# Display_Alt.net
KiCad netlist of a schematic drawn in Altium Designer
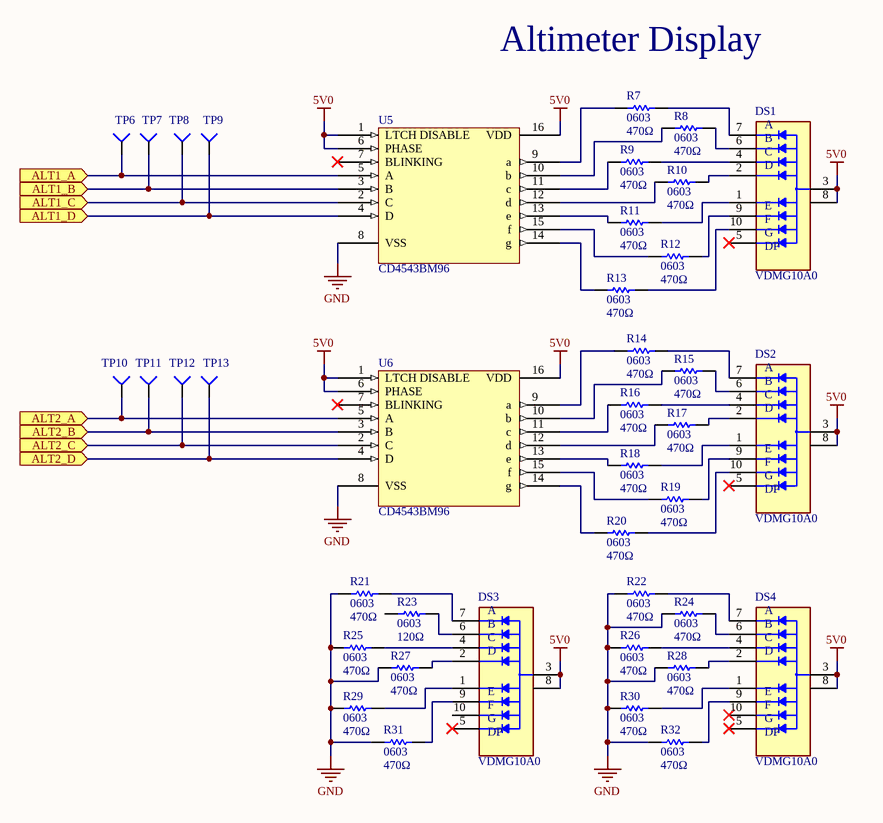
[diagram p0: Display Alt.SchDoc]

(export (version "E")
  (design (tool "Eeschema 10.0.6"))
  (components
    (comp (ref "DS1")
      (value "VDMG10A0")
      (footprint "DISPLAY_VDMG10A0")
      (description "Smart/Normal 7 Seg Numeric LED Display")
      (fields (field (name "MANUFACTURER") "Vishay Semiconductors"))
      (libsource (lib "SKALE_LIB") (part "7 SEG DISPLAY - VDMG10A0"))
    )
    (comp (ref "DS2")
      (value "VDMG10A0")
      (footprint "DISPLAY_VDMG10A0")
      (description "Smart/Normal 7 Seg Numeric LED Display")
      (fields (field (name "MANUFACTURER") "Vishay Semiconductors"))
      (libsource (lib "SKALE_LIB") (part "7 SEG DISPLAY - VDMG10A0"))
    )
    (comp (ref "DS3")
      (value "VDMG10A0")
      (footprint "DISPLAY_VDMG10A0")
      (description "Smart/Normal 7 Seg Numeric LED Display")
      (fields (field (name "MANUFACTURER") "Vishay Semiconductors"))
      (libsource (lib "SKALE_LIB") (part "7 SEG DISPLAY - VDMG10A0"))
    )
    (comp (ref "DS4")
      (value "VDMG10A0")
      (footprint "DISPLAY_VDMG10A0")
      (description "Smart/Normal 7 Seg Numeric LED Display")
      (fields (field (name "MANUFACTURER") "Vishay Semiconductors"))
      (libsource (lib "SKALE_LIB") (part "7 SEG DISPLAY - VDMG10A0"))
    )
    (comp (ref "R7")
      (value "470Ω")
      (footprint "RES0603")
      (description "RES 470 OHM 1% 1/10W 0603")
      (fields (field (name "FOOTPRINT SIZE") "0603") (field (name "Comment") "470R 1%"))
      (libsource (lib "SKALE_LIB") (part "RES_470Ω_0603_1%"))
    )
    (comp (ref "R8")
      (value "470Ω")
      (footprint "RES0603")
      (description "RES 470 OHM 1% 1/10W 0603")
      (fields (field (name "FOOTPRINT SIZE") "0603") (field (name "Comment") "470R 1%"))
      (libsource (lib "SKALE_LIB") (part "RES_470Ω_0603_1%"))
    )
    (comp (ref "R9")
      (value "470Ω")
      (footprint "RES0603")
      (description "RES 470 OHM 1% 1/10W 0603")
      (fields (field (name "FOOTPRINT SIZE") "0603") (field (name "Comment") "470R 1%"))
      (libsource (lib "SKALE_LIB") (part "RES_470Ω_0603_1%"))
    )
    (comp (ref "R10")
      (value "470Ω")
      (footprint "RES0603")
      (description "RES 470 OHM 1% 1/10W 0603")
      (fields (field (name "FOOTPRINT SIZE") "0603") (field (name "Comment") "470R 1%"))
      (libsource (lib "SKALE_LIB") (part "RES_470Ω_0603_1%"))
    )
    (comp (ref "R11")
      (value "470Ω")
      (footprint "RES0603")
      (description "RES 470 OHM 1% 1/10W 0603")
      (fields (field (name "FOOTPRINT SIZE") "0603") (field (name "Comment") "470R 1%"))
      (libsource (lib "SKALE_LIB") (part "RES_470Ω_0603_1%"))
    )
    (comp (ref "R12")
      (value "470Ω")
      (footprint "RES0603")
      (description "RES 470 OHM 1% 1/10W 0603")
      (fields (field (name "FOOTPRINT SIZE") "0603") (field (name "Comment") "470R 1%"))
      (libsource (lib "SKALE_LIB") (part "RES_470Ω_0603_1%"))
    )
    (comp (ref "R13")
      (value "470Ω")
      (footprint "RES0603")
      (description "RES 470 OHM 1% 1/10W 0603")
      (fields (field (name "FOOTPRINT SIZE") "0603") (field (name "Comment") "470R 1%"))
      (libsource (lib "SKALE_LIB") (part "RES_470Ω_0603_1%"))
    )
    (comp (ref "R14")
      (value "470Ω")
      (footprint "RES0603")
      (description "RES 470 OHM 1% 1/10W 0603")
      (fields (field (name "FOOTPRINT SIZE") "0603") (field (name "Comment") "470R 1%"))
      (libsource (lib "SKALE_LIB") (part "RES_470Ω_0603_1%"))
    )
    (comp (ref "R15")
      (value "470Ω")
      (footprint "RES0603")
      (description "RES 470 OHM 1% 1/10W 0603")
      (fields (field (name "FOOTPRINT SIZE") "0603") (field (name "Comment") "470R 1%"))
      (libsource (lib "SKALE_LIB") (part "RES_470Ω_0603_1%"))
    )
    (comp (ref "R16")
      (value "470Ω")
      (footprint "RES0603")
      (description "RES 470 OHM 1% 1/10W 0603")
      (fields (field (name "FOOTPRINT SIZE") "0603") (field (name "Comment") "470R 1%"))
      (libsource (lib "SKALE_LIB") (part "RES_470Ω_0603_1%"))
    )
    (comp (ref "R17")
      (value "470Ω")
      (footprint "RES0603")
      (description "RES 470 OHM 1% 1/10W 0603")
      (fields (field (name "FOOTPRINT SIZE") "0603") (field (name "Comment") "470R 1%"))
      (libsource (lib "SKALE_LIB") (part "RES_470Ω_0603_1%"))
    )
    (comp (ref "R18")
      (value "470Ω")
      (footprint "RES0603")
      (description "RES 470 OHM 1% 1/10W 0603")
      (fields (field (name "FOOTPRINT SIZE") "0603") (field (name "Comment") "470R 1%"))
      (libsource (lib "SKALE_LIB") (part "RES_470Ω_0603_1%"))
    )
    (comp (ref "R19")
      (value "470Ω")
      (footprint "RES0603")
      (description "RES 470 OHM 1% 1/10W 0603")
      (fields (field (name "FOOTPRINT SIZE") "0603") (field (name "Comment") "470R 1%"))
      (libsource (lib "SKALE_LIB") (part "RES_470Ω_0603_1%"))
    )
    (comp (ref "R20")
      (value "470Ω")
      (footprint "RES0603")
      (description "RES 470 OHM 1% 1/10W 0603")
      (fields (field (name "FOOTPRINT SIZE") "0603") (field (name "Comment") "470R 1%"))
      (libsource (lib "SKALE_LIB") (part "RES_470Ω_0603_1%"))
    )
    (comp (ref "R21")
      (value "470Ω")
      (footprint "RES0603")
      (description "RES 470 OHM 1% 1/10W 0603")
      (fields (field (name "FOOTPRINT SIZE") "0603") (field (name "Comment") "470R 1%"))
      (libsource (lib "SKALE_LIB") (part "RES_470Ω_0603_1%"))
    )
    (comp (ref "R22")
      (value "470Ω")
      (footprint "RES0603")
      (description "RES 470 OHM 1% 1/10W 0603")
      (fields (field (name "FOOTPRINT SIZE") "0603") (field (name "Comment") "470R 1%"))
      (libsource (lib "SKALE_LIB") (part "RES_470Ω_0603_1%"))
    )
    (comp (ref "R23")
      (value "120Ω")
      (footprint "RES0603")
      (description "RES 120 OHM 5% 1/10W 0603")
      (fields (field (name "PACKAGE/FOOTPRINT") "0603") (field (name "Comment") "RES_120Ω_0603"))
      (libsource (lib "SKALE_LIB") (part "RES_120Ω_0603_5%"))
    )
    (comp (ref "R24")
      (value "470Ω")
      (footprint "RES0603")
      (description "RES 470 OHM 1% 1/10W 0603")
      (fields (field (name "FOOTPRINT SIZE") "0603") (field (name "Comment") "470R 1%"))
      (libsource (lib "SKALE_LIB") (part "RES_470Ω_0603_1%"))
    )
    (comp (ref "R25")
      (value "470Ω")
      (footprint "RES0603")
      (description "RES 470 OHM 1% 1/10W 0603")
      (fields (field (name "FOOTPRINT SIZE") "0603") (field (name "Comment") "470R 1%"))
      (libsource (lib "SKALE_LIB") (part "RES_470Ω_0603_1%"))
    )
    (comp (ref "R26")
      (value "470Ω")
      (footprint "RES0603")
      (description "RES 470 OHM 1% 1/10W 0603")
      (fields (field (name "FOOTPRINT SIZE") "0603") (field (name "Comment") "470R 1%"))
      (libsource (lib "SKALE_LIB") (part "RES_470Ω_0603_1%"))
    )
    (comp (ref "R27")
      (value "470Ω")
      (footprint "RES0603")
      (description "RES 470 OHM 1% 1/10W 0603")
      (fields (field (name "FOOTPRINT SIZE") "0603") (field (name "Comment") "470R 1%"))
      (libsource (lib "SKALE_LIB") (part "RES_470Ω_0603_1%"))
    )
    (comp (ref "R28")
      (value "470Ω")
      (footprint "RES0603")
      (description "RES 470 OHM 1% 1/10W 0603")
      (fields (field (name "FOOTPRINT SIZE") "0603") (field (name "Comment") "470R 1%"))
      (libsource (lib "SKALE_LIB") (part "RES_470Ω_0603_1%"))
    )
    (comp (ref "R29")
      (value "470Ω")
      (footprint "RES0603")
      (description "RES 470 OHM 1% 1/10W 0603")
      (fields (field (name "FOOTPRINT SIZE") "0603") (field (name "Comment") "470R 1%"))
      (libsource (lib "SKALE_LIB") (part "RES_470Ω_0603_1%"))
    )
    (comp (ref "R30")
      (value "470Ω")
      (footprint "RES0603")
      (description "RES 470 OHM 1% 1/10W 0603")
      (fields (field (name "FOOTPRINT SIZE") "0603") (field (name "Comment") "470R 1%"))
      (libsource (lib "SKALE_LIB") (part "RES_470Ω_0603_1%"))
    )
    (comp (ref "R31")
      (value "470Ω")
      (footprint "RES0603")
      (description "RES 470 OHM 1% 1/10W 0603")
      (fields (field (name "FOOTPRINT SIZE") "0603") (field (name "Comment") "470R 1%"))
      (libsource (lib "SKALE_LIB") (part "RES_470Ω_0603_1%"))
    )
    (comp (ref "R32")
      (value "470Ω")
      (footprint "RES0603")
      (description "RES 470 OHM 1% 1/10W 0603")
      (fields (field (name "FOOTPRINT SIZE") "0603") (field (name "Comment") "470R 1%"))
      (libsource (lib "SKALE_LIB") (part "RES_470Ω_0603_1%"))
    )
    (comp (ref "TP6")
      (value "TESTPT")
      (footprint "TESTPT SQUARE")
      (libsource (lib "SKALE_LIB") (part "TESTPT SQUARE"))
    )
    (comp (ref "TP7")
      (value "TESTPT")
      (footprint "TESTPT SQUARE")
      (libsource (lib "SKALE_LIB") (part "TESTPT SQUARE"))
    )
    (comp (ref "TP8")
      (value "TESTPT")
      (footprint "TESTPT SQUARE")
      (libsource (lib "SKALE_LIB") (part "TESTPT SQUARE"))
    )
    (comp (ref "TP9")
      (value "TESTPT")
      (footprint "TESTPT SQUARE")
      (libsource (lib "SKALE_LIB") (part "TESTPT SQUARE"))
    )
    (comp (ref "TP10")
      (value "TESTPT")
      (footprint "TESTPT SQUARE")
      (libsource (lib "SKALE_LIB") (part "TESTPT SQUARE"))
    )
    (comp (ref "TP11")
      (value "TESTPT")
      (footprint "TESTPT SQUARE")
      (libsource (lib "SKALE_LIB") (part "TESTPT SQUARE"))
    )
    (comp (ref "TP12")
      (value "TESTPT")
      (footprint "TESTPT SQUARE")
      (libsource (lib "SKALE_LIB") (part "TESTPT SQUARE"))
    )
    (comp (ref "TP13")
      (value "TESTPT")
      (footprint "TESTPT SQUARE")
      (libsource (lib "SKALE_LIB") (part "TESTPT SQUARE"))
    )
    (comp (ref "U5")
      (value "CD4543BM96")
      (footprint "SOIC127P600X175-16N")
      (description "Seven Segment Decoder/Driver, 4000/14000/40000 Series, Configurable Output, CMOS, PDSO16")
      (fields (field (name "MANUFACTURER") "Texas Instruments"))
      (libsource (lib "SKALE_LIB") (part "7 SEG DISPLAY IC"))
    )
    (comp (ref "U6")
      (value "CD4543BM96")
      (footprint "SOIC127P600X175-16N")
      (description "Seven Segment Decoder/Driver, 4000/14000/40000 Series, Configurable Output, CMOS, PDSO16")
      (fields (field (name "MANUFACTURER") "Texas Instruments"))
      (libsource (lib "SKALE_LIB") (part "7 SEG DISPLAY IC"))
    )
  )
  (nets
    (net (code "1") (name "/ALT1_A") (class "Default")
      (node (ref "TP6") (pin "1") (pinfunction "=value_1") (pintype "passive"))
      (node (ref "U5") (pin "5") (pinfunction "A_5") (pintype "input"))
    )
    (net (code "2") (name "/ALT1_B") (class "Default")
      (node (ref "TP7") (pin "1") (pinfunction "=value_1") (pintype "passive"))
      (node (ref "U5") (pin "3") (pinfunction "B_3") (pintype "input"))
    )
    (net (code "3") (name "/ALT1_C") (class "Default")
      (node (ref "TP8") (pin "1") (pinfunction "=value_1") (pintype "passive"))
      (node (ref "U5") (pin "2") (pinfunction "C_2") (pintype "input"))
    )
    (net (code "4") (name "/ALT1_D") (class "Default")
      (node (ref "TP9") (pin "1") (pinfunction "=value_1") (pintype "passive"))
      (node (ref "U5") (pin "4") (pinfunction "D_4") (pintype "input"))
    )
    (net (code "5") (name "/ALT2_A") (class "Default")
      (node (ref "TP10") (pin "1") (pinfunction "=value_1") (pintype "passive"))
      (node (ref "U6") (pin "5") (pinfunction "A_5") (pintype "input"))
    )
    (net (code "6") (name "/ALT2_B") (class "Default")
      (node (ref "TP11") (pin "1") (pinfunction "=value_1") (pintype "passive"))
      (node (ref "U6") (pin "3") (pinfunction "B_3") (pintype "input"))
    )
    (net (code "7") (name "/ALT2_C") (class "Default")
      (node (ref "TP12") (pin "1") (pinfunction "=value_1") (pintype "passive"))
      (node (ref "U6") (pin "2") (pinfunction "C_2") (pintype "input"))
    )
    (net (code "8") (name "/ALT2_D") (class "Default")
      (node (ref "TP13") (pin "1") (pinfunction "=value_1") (pintype "passive"))
      (node (ref "U6") (pin "4") (pinfunction "D_4") (pintype "input"))
    )
    (net (code "9") (name "5V0") (class "Default")
      (node (ref "DS1") (pin "3") (pinfunction "ANODE_3") (pintype "passive"))
      (node (ref "DS1") (pin "8") (pinfunction "ANODE_8") (pintype "passive"))
      (node (ref "DS2") (pin "3") (pinfunction "ANODE_3") (pintype "passive"))
      (node (ref "DS2") (pin "8") (pinfunction "ANODE_8") (pintype "passive"))
      (node (ref "DS3") (pin "3") (pinfunction "ANODE_3") (pintype "passive"))
      (node (ref "DS3") (pin "8") (pinfunction "ANODE_8") (pintype "passive"))
      (node (ref "DS4") (pin "3") (pinfunction "ANODE_3") (pintype "passive"))
      (node (ref "DS4") (pin "8") (pinfunction "ANODE_8") (pintype "passive"))
      (node (ref "U5") (pin "1") (pinfunction "LTCH_DISABLE_1") (pintype "input"))
      (node (ref "U5") (pin "16") (pinfunction "VDD_16") (pintype "power_in"))
      (node (ref "U5") (pin "6") (pinfunction "PHASE_6") (pintype "input"))
      (node (ref "U6") (pin "1") (pinfunction "LTCH_DISABLE_1") (pintype "input"))
      (node (ref "U6") (pin "16") (pinfunction "VDD_16") (pintype "power_in"))
      (node (ref "U6") (pin "6") (pinfunction "PHASE_6") (pintype "input"))
    )
    (net (code "10") (name "GND") (class "Default")
      (node (ref "R21") (pin "1") (pinfunction "1_1") (pintype "passive"))
      (node (ref "R22") (pin "1") (pinfunction "1_1") (pintype "passive"))
      (node (ref "R24") (pin "1") (pinfunction "1_1") (pintype "passive"))
      (node (ref "R25") (pin "1") (pinfunction "1_1") (pintype "passive"))
      (node (ref "R26") (pin "1") (pinfunction "1_1") (pintype "passive"))
      (node (ref "R27") (pin "1") (pinfunction "1_1") (pintype "passive"))
      (node (ref "R28") (pin "1") (pinfunction "1_1") (pintype "passive"))
      (node (ref "R29") (pin "1") (pinfunction "1_1") (pintype "passive"))
      (node (ref "R30") (pin "1") (pinfunction "1_1") (pintype "passive"))
      (node (ref "R31") (pin "1") (pinfunction "1_1") (pintype "passive"))
      (node (ref "R32") (pin "1") (pinfunction "1_1") (pintype "passive"))
      (node (ref "U5") (pin "8") (pinfunction "VSS_8") (pintype "power_in"))
      (node (ref "U6") (pin "8") (pinfunction "VSS_8") (pintype "power_in"))
    )
    (net (code "11") (name "Net-(DS1-A)") (class "Default")
      (node (ref "DS1") (pin "7") (pinfunction "A_7") (pintype "passive"))
      (node (ref "R7") (pin "2") (pinfunction "2_2") (pintype "passive"))
    )
    (net (code "12") (name "Net-(DS1-B)") (class "Default")
      (node (ref "DS1") (pin "6") (pinfunction "B_6") (pintype "passive"))
      (node (ref "R8") (pin "2") (pinfunction "2_2") (pintype "passive"))
    )
    (net (code "13") (name "Net-(DS1-C)") (class "Default")
      (node (ref "DS1") (pin "4") (pinfunction "C_4") (pintype "passive"))
      (node (ref "R9") (pin "2") (pinfunction "2_2") (pintype "passive"))
    )
    (net (code "14") (name "Net-(DS1-D)") (class "Default")
      (node (ref "DS1") (pin "2") (pinfunction "D_2") (pintype "passive"))
      (node (ref "R10") (pin "2") (pinfunction "2_2") (pintype "passive"))
    )
    (net (code "15") (name "Net-(DS1-E)") (class "Default")
      (node (ref "DS1") (pin "1") (pinfunction "E_1") (pintype "passive"))
      (node (ref "R11") (pin "2") (pinfunction "2_2") (pintype "passive"))
    )
    (net (code "16") (name "Net-(DS1-F)") (class "Default")
      (node (ref "DS1") (pin "9") (pinfunction "F_9") (pintype "passive"))
      (node (ref "R12") (pin "2") (pinfunction "2_2") (pintype "passive"))
    )
    (net (code "17") (name "Net-(DS1-G)") (class "Default")
      (node (ref "DS1") (pin "10") (pinfunction "G_10") (pintype "passive"))
      (node (ref "R13") (pin "2") (pinfunction "2_2") (pintype "passive"))
    )
    (net (code "18") (name "Net-(DS2-A)") (class "Default")
      (node (ref "DS2") (pin "7") (pinfunction "A_7") (pintype "passive"))
      (node (ref "R14") (pin "2") (pinfunction "2_2") (pintype "passive"))
    )
    (net (code "19") (name "Net-(DS2-B)") (class "Default")
      (node (ref "DS2") (pin "6") (pinfunction "B_6") (pintype "passive"))
      (node (ref "R15") (pin "2") (pinfunction "2_2") (pintype "passive"))
    )
    (net (code "20") (name "Net-(DS2-C)") (class "Default")
      (node (ref "DS2") (pin "4") (pinfunction "C_4") (pintype "passive"))
      (node (ref "R16") (pin "2") (pinfunction "2_2") (pintype "passive"))
    )
    (net (code "21") (name "Net-(DS2-D)") (class "Default")
      (node (ref "DS2") (pin "2") (pinfunction "D_2") (pintype "passive"))
      (node (ref "R17") (pin "2") (pinfunction "2_2") (pintype "passive"))
    )
    (net (code "22") (name "Net-(DS2-E)") (class "Default")
      (node (ref "DS2") (pin "1") (pinfunction "E_1") (pintype "passive"))
      (node (ref "R18") (pin "2") (pinfunction "2_2") (pintype "passive"))
    )
    (net (code "23") (name "Net-(DS2-F)") (class "Default")
      (node (ref "DS2") (pin "9") (pinfunction "F_9") (pintype "passive"))
      (node (ref "R19") (pin "2") (pinfunction "2_2") (pintype "passive"))
    )
    (net (code "24") (name "Net-(DS2-G)") (class "Default")
      (node (ref "DS2") (pin "10") (pinfunction "G_10") (pintype "passive"))
      (node (ref "R20") (pin "2") (pinfunction "2_2") (pintype "passive"))
    )
    (net (code "25") (name "Net-(DS3-A)") (class "Default")
      (node (ref "DS3") (pin "7") (pinfunction "A_7") (pintype "passive"))
      (node (ref "R21") (pin "2") (pinfunction "2_2") (pintype "passive"))
    )
    (net (code "26") (name "Net-(DS3-B)") (class "Default")
      (node (ref "DS3") (pin "6") (pinfunction "B_6") (pintype "passive"))
      (node (ref "R23") (pin "2") (pinfunction "2_2") (pintype "passive"))
    )
    (net (code "27") (name "Net-(DS3-C)") (class "Default")
      (node (ref "DS3") (pin "4") (pinfunction "C_4") (pintype "passive"))
      (node (ref "R25") (pin "2") (pinfunction "2_2") (pintype "passive"))
    )
    (net (code "28") (name "Net-(DS3-D)") (class "Default")
      (node (ref "DS3") (pin "2") (pinfunction "D_2") (pintype "passive"))
      (node (ref "R27") (pin "2") (pinfunction "2_2") (pintype "passive"))
    )
    (net (code "29") (name "Net-(DS3-E)") (class "Default")
      (node (ref "DS3") (pin "1") (pinfunction "E_1") (pintype "passive"))
      (node (ref "R29") (pin "2") (pinfunction "2_2") (pintype "passive"))
    )
    (net (code "30") (name "Net-(DS3-F)") (class "Default")
      (node (ref "DS3") (pin "9") (pinfunction "F_9") (pintype "passive"))
      (node (ref "R31") (pin "2") (pinfunction "2_2") (pintype "passive"))
    )
    (net (code "31") (name "Net-(DS4-A)") (class "Default")
      (node (ref "DS4") (pin "7") (pinfunction "A_7") (pintype "passive"))
      (node (ref "R22") (pin "2") (pinfunction "2_2") (pintype "passive"))
    )
    (net (code "32") (name "Net-(DS4-B)") (class "Default")
      (node (ref "DS4") (pin "6") (pinfunction "B_6") (pintype "passive"))
      (node (ref "R24") (pin "2") (pinfunction "2_2") (pintype "passive"))
    )
    (net (code "33") (name "Net-(DS4-C)") (class "Default")
      (node (ref "DS4") (pin "4") (pinfunction "C_4") (pintype "passive"))
      (node (ref "R26") (pin "2") (pinfunction "2_2") (pintype "passive"))
    )
    (net (code "34") (name "Net-(DS4-D)") (class "Default")
      (node (ref "DS4") (pin "2") (pinfunction "D_2") (pintype "passive"))
      (node (ref "R28") (pin "2") (pinfunction "2_2") (pintype "passive"))
    )
    (net (code "35") (name "Net-(DS4-E)") (class "Default")
      (node (ref "DS4") (pin "1") (pinfunction "E_1") (pintype "passive"))
      (node (ref "R30") (pin "2") (pinfunction "2_2") (pintype "passive"))
    )
    (net (code "36") (name "Net-(DS4-F)") (class "Default")
      (node (ref "DS4") (pin "9") (pinfunction "F_9") (pintype "passive"))
      (node (ref "R32") (pin "2") (pinfunction "2_2") (pintype "passive"))
    )
    (net (code "37") (name "Net-(U5-a)") (class "Default")
      (node (ref "R7") (pin "1") (pinfunction "1_1") (pintype "passive"))
      (node (ref "U5") (pin "9") (pinfunction "a_9") (pintype "output"))
    )
    (net (code "38") (name "Net-(U5-b)") (class "Default")
      (node (ref "R8") (pin "1") (pinfunction "1_1") (pintype "passive"))
      (node (ref "U5") (pin "10") (pinfunction "b_10") (pintype "output"))
    )
    (net (code "39") (name "Net-(U5-c)") (class "Default")
      (node (ref "R9") (pin "1") (pinfunction "1_1") (pintype "passive"))
      (node (ref "U5") (pin "11") (pinfunction "c_11") (pintype "output"))
    )
    (net (code "40") (name "Net-(U5-d)") (class "Default")
      (node (ref "R10") (pin "1") (pinfunction "1_1") (pintype "passive"))
      (node (ref "U5") (pin "12") (pinfunction "d_12") (pintype "output"))
    )
    (net (code "41") (name "Net-(U5-e)") (class "Default")
      (node (ref "R11") (pin "1") (pinfunction "1_1") (pintype "passive"))
      (node (ref "U5") (pin "13") (pinfunction "e_13") (pintype "output"))
    )
    (net (code "42") (name "Net-(U5-f)") (class "Default")
      (node (ref "R12") (pin "1") (pinfunction "1_1") (pintype "passive"))
      (node (ref "U5") (pin "15") (pinfunction "f_15") (pintype "output"))
    )
    (net (code "43") (name "Net-(U5-g)") (class "Default")
      (node (ref "R13") (pin "1") (pinfunction "1_1") (pintype "passive"))
      (node (ref "U5") (pin "14") (pinfunction "g_14") (pintype "output"))
    )
    (net (code "44") (name "Net-(U6-a)") (class "Default")
      (node (ref "R14") (pin "1") (pinfunction "1_1") (pintype "passive"))
      (node (ref "U6") (pin "9") (pinfunction "a_9") (pintype "output"))
    )
    (net (code "45") (name "Net-(U6-b)") (class "Default")
      (node (ref "R15") (pin "1") (pinfunction "1_1") (pintype "passive"))
      (node (ref "U6") (pin "10") (pinfunction "b_10") (pintype "output"))
    )
    (net (code "46") (name "Net-(U6-c)") (class "Default")
      (node (ref "R16") (pin "1") (pinfunction "1_1") (pintype "passive"))
      (node (ref "U6") (pin "11") (pinfunction "c_11") (pintype "output"))
    )
    (net (code "47") (name "Net-(U6-d)") (class "Default")
      (node (ref "R17") (pin "1") (pinfunction "1_1") (pintype "passive"))
      (node (ref "U6") (pin "12") (pinfunction "d_12") (pintype "output"))
    )
    (net (code "48") (name "Net-(U6-e)") (class "Default")
      (node (ref "R18") (pin "1") (pinfunction "1_1") (pintype "passive"))
      (node (ref "U6") (pin "13") (pinfunction "e_13") (pintype "output"))
    )
    (net (code "49") (name "Net-(U6-f)") (class "Default")
      (node (ref "R19") (pin "1") (pinfunction "1_1") (pintype "passive"))
      (node (ref "U6") (pin "15") (pinfunction "f_15") (pintype "output"))
    )
    (net (code "50") (name "Net-(U6-g)") (class "Default")
      (node (ref "R20") (pin "1") (pinfunction "1_1") (pintype "passive"))
      (node (ref "U6") (pin "14") (pinfunction "g_14") (pintype "output"))
    )
    (net (code "51") (name "unconnected-(DS1-DP-Pad5)") (class "Default")
      (node (ref "DS1") (pin "5") (pinfunction "DP_5") (pintype "passive+no_connect"))
    )
    (net (code "52") (name "unconnected-(DS2-DP-Pad5)") (class "Default")
      (node (ref "DS2") (pin "5") (pinfunction "DP_5") (pintype "passive+no_connect"))
    )
    (net (code "53") (name "unconnected-(DS3-DP-Pad5)") (class "Default")
      (node (ref "DS3") (pin "5") (pinfunction "DP_5") (pintype "passive+no_connect"))
    )
    (net (code "54") (name "unconnected-(DS3-G-Pad10)") (class "Default")
      (node (ref "DS3") (pin "10") (pinfunction "G_10") (pintype "passive"))
    )
    (net (code "55") (name "unconnected-(DS4-DP-Pad5)") (class "Default")
      (node (ref "DS4") (pin "5") (pinfunction "DP_5") (pintype "passive+no_connect"))
    )
    (net (code "56") (name "unconnected-(DS4-G-Pad10)") (class "Default")
      (node (ref "DS4") (pin "10") (pinfunction "G_10") (pintype "passive+no_connect"))
    )
    (net (code "57") (name "unconnected-(R23-Pad1)") (class "Default")
      (node (ref "R23") (pin "1") (pinfunction "1_1") (pintype "passive"))
    )
    (net (code "58") (name "unconnected-(U5-BLINKING-Pad7)") (class "Default")
      (node (ref "U5") (pin "7") (pinfunction "BLINKING_7") (pintype "input+no_connect"))
    )
    (net (code "59") (name "unconnected-(U6-BLINKING-Pad7)") (class "Default")
      (node (ref "U6") (pin "7") (pinfunction "BLINKING_7") (pintype "input+no_connect"))
    )
  )
)
